# untitled.net
KiCad netlist of a schematic drawn in EAGLE
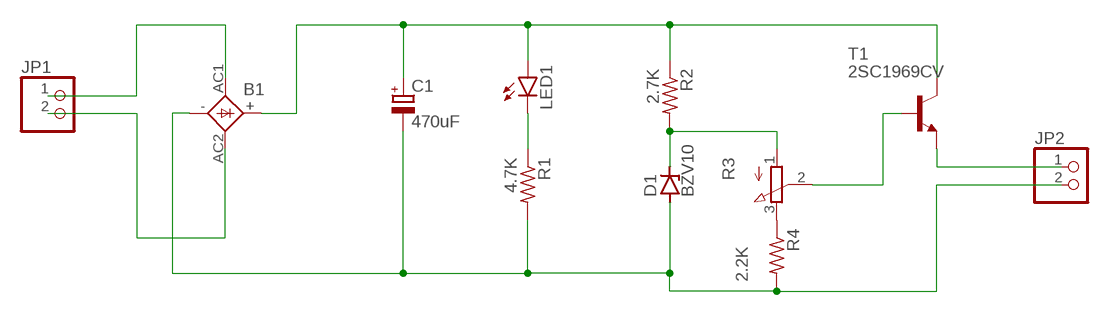
[diagram p0: schematic, sheet 1]

(export (version "E")
  (design (tool "Eeschema 10.0.6"))
  (components
    (comp (ref "B1")
      (value "1KAB")
      (footprint "eagle-import:1KAB")
      (libsource (lib "eagle-import") (part "1KAB"))
    )
    (comp (ref "C1")
      (value "470uF")
      (footprint "eagle-import:E3,5-10")
      (libsource (lib "eagle-import") (part "CPOL-EUE3.5-10"))
    )
    (comp (ref "D1")
      (value "BZV10")
      (footprint "eagle-import:DO34Z7")
      (libsource (lib "eagle-import") (part "BZV10"))
    )
    (comp (ref "JP1")
      (value "PINHD-1X2")
      (footprint "eagle-import:1X02")
      (libsource (lib "eagle-import") (part "PINHD-1X2"))
    )
    (comp (ref "JP2")
      (value "PINHD-1X2")
      (footprint "eagle-import:1X02")
      (libsource (lib "eagle-import") (part "PINHD-1X2"))
    )
    (comp (ref "LED1")
      (value "LED5MM")
      (footprint "eagle-import:LED5MM")
      (libsource (lib "eagle-import") (part "LED5MM"))
    )
    (comp (ref "R1")
      (value "4.7K")
      (footprint "eagle-import:0309_12")
      (libsource (lib "eagle-import") (part "R-US_0309/12"))
    )
    (comp (ref "R2")
      (value "2.7K")
      (footprint "eagle-import:0309_12")
      (libsource (lib "eagle-import") (part "R-US_0309/12"))
    )
    (comp (ref "R3")
      (value "3RP/1610N")
      (footprint "eagle-import:3RP_1610N")
      (libsource (lib "eagle-import") (part "3RP/1610N"))
    )
    (comp (ref "R4")
      (value "2.2K")
      (footprint "eagle-import:0309_12")
      (libsource (lib "eagle-import") (part "R-US_0309/12"))
    )
    (comp (ref "T1")
      (value "2SC1969CV")
      (footprint "eagle-import:T-30_V")
      (libsource (lib "eagle-import") (part "2SC1969VC"))
    )
  )
  (nets
    (net (code "1") (name "Net-(B1-Pad-)") (class "Default")
      (node (ref "B1") (pin "-") (pinfunction "-_-") (pintype "passive"))
      (node (ref "C1") (pin "-") (pinfunction "-_-") (pintype "passive"))
      (node (ref "D1") (pin "A") (pinfunction "A_A") (pintype "passive"))
      (node (ref "JP2") (pin "2") (pinfunction "2_2") (pintype "passive"))
      (node (ref "R1") (pin "2") (pinfunction "2_2") (pintype "passive"))
      (node (ref "R4") (pin "2") (pinfunction "2_2") (pintype "passive"))
    )
    (net (code "2") (name "Net-(B1-PadAC1)") (class "Default")
      (node (ref "B1") (pin "AC1") (pinfunction "AC1_AC1") (pintype "passive"))
      (node (ref "JP1") (pin "1") (pinfunction "1_1") (pintype "passive"))
    )
    (net (code "3") (name "Net-(B1-PadAC2)") (class "Default")
      (node (ref "B1") (pin "AC2") (pinfunction "AC2_AC2") (pintype "passive"))
      (node (ref "JP1") (pin "2") (pinfunction "2_2") (pintype "passive"))
    )
    (net (code "4") (name "Net-(LED1-C)") (class "Default")
      (node (ref "LED1") (pin "K") (pinfunction "C_K") (pintype "passive"))
      (node (ref "R1") (pin "1") (pinfunction "1_1") (pintype "passive"))
    )
    (net (code "5") (name "Net-(R3-A)") (class "Default")
      (node (ref "D1") (pin "C") (pinfunction "C_C") (pintype "passive"))
      (node (ref "R2") (pin "2") (pinfunction "2_2") (pintype "passive"))
      (node (ref "R3") (pin "1") (pinfunction "A_1") (pintype "passive"))
    )
    (net (code "6") (name "Net-(R3-E)") (class "Default")
      (node (ref "R3") (pin "3") (pinfunction "E_3") (pintype "passive"))
      (node (ref "R4") (pin "1") (pinfunction "1_1") (pintype "passive"))
    )
    (net (code "7") (name "Net-(R3-S)") (class "Default")
      (node (ref "R3") (pin "2") (pinfunction "S_2") (pintype "passive"))
      (node (ref "T1") (pin "1") (pinfunction "B_1") (pintype "passive"))
    )
    (net (code "8") (name "Net-(T1-C)") (class "Default")
      (node (ref "B1") (pin "+") (pinfunction "+_+") (pintype "passive"))
      (node (ref "C1") (pin "+") (pinfunction "+_+") (pintype "passive"))
      (node (ref "LED1") (pin "A") (pinfunction "A_A") (pintype "passive"))
      (node (ref "R2") (pin "1") (pinfunction "1_1") (pintype "passive"))
      (node (ref "T1") (pin "2") (pinfunction "C_2") (pintype "passive"))
    )
    (net (code "9") (name "Net-(T1-E)") (class "Default")
      (node (ref "JP2") (pin "1") (pinfunction "1_1") (pintype "passive"))
      (node (ref "T1") (pin "3") (pinfunction "E_3") (pintype "passive"))
    )
  )
)
